# Sheet1.net
KiCad netlist of a schematic drawn in Altium Designer
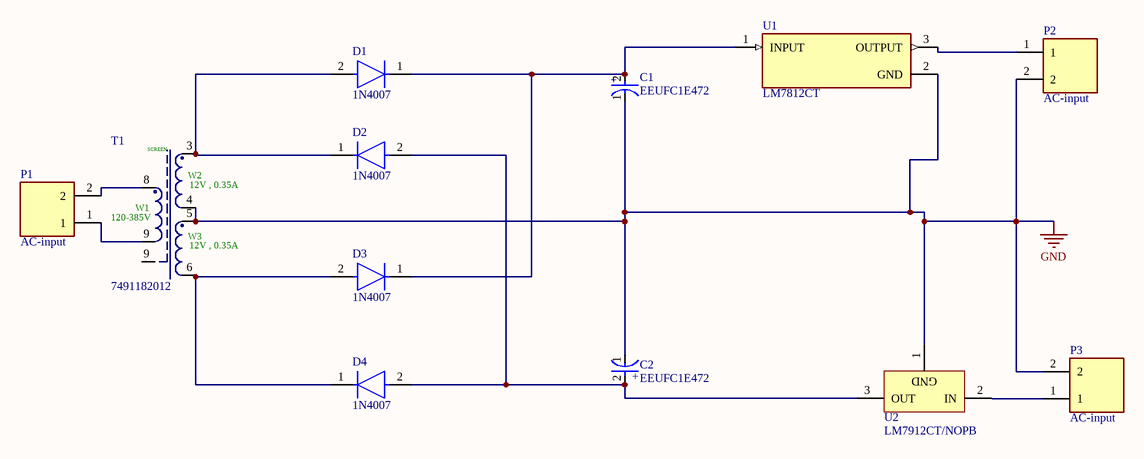
[diagram p0: Sheet1.SchDoc]

(export (version "E")
  (design (tool "Eeschema 10.0.6"))
  (components
    (comp (ref "C1")
      (value "EEUFC1E472")
      (footprint "FP-RAD-TH-D_18_0_5-L_35_5-MFG")
      (description "Aluminum Electrolytic Capacitors (Radial Lead Type) AEC-Q200 Qualified 4700uF ±20% 25V")
      (fields (field (name "VOLTAGE") "25V") (field (name "TOLERANCE") "20%"))
      (libsource (lib "Altium Content Vault") (part "203bc49f2ac43e59fd269a8c329ed05"))
    )
    (comp (ref "C2")
      (value "EEUFC1E472")
      (footprint "FP-RAD-TH-D_18_0_5-L_35_5-MFG")
      (description "Aluminum Electrolytic Capacitors (Radial Lead Type) AEC-Q200 Qualified 4700uF ±20% 25V")
      (fields (field (name "VOLTAGE") "25V") (field (name "TOLERANCE") "20%"))
      (libsource (lib "Altium Content Vault") (part "203bc49f2ac43e59fd269a8c329ed05"))
    )
    (comp (ref "D1")
      (value "1N4007")
      (footprint "FP-1N4007-MFG")
      (description "Rectifier diode 1000 V 1 A DO-41, ,")
      (fields
        (field (name "MANUFACTURER") "Diotec")
        (field (name "OCTOPART") "https://octopart.com/1n4007-diotec-4040411")
      )
      (libsource (lib "Altium Content Vault") (part "d7152d700b627762746794eb795d46e"))
    )
    (comp (ref "D2")
      (value "1N4007")
      (footprint "FP-1N4007-MFG")
      (description "Rectifier diode 1000 V 1 A DO-41, ,")
      (fields
        (field (name "MANUFACTURER") "Diotec")
        (field (name "OCTOPART") "https://octopart.com/1n4007-diotec-4040411")
      )
      (libsource (lib "Altium Content Vault") (part "d7152d700b627762746794eb795d46e"))
    )
    (comp (ref "D3")
      (value "1N4007")
      (footprint "FP-1N4007-MFG")
      (description "Rectifier diode 1000 V 1 A DO-41, ,")
      (fields
        (field (name "MANUFACTURER") "Diotec")
        (field (name "OCTOPART") "https://octopart.com/1n4007-diotec-4040411")
      )
      (libsource (lib "Altium Content Vault") (part "d7152d700b627762746794eb795d46e"))
    )
    (comp (ref "D4")
      (value "1N4007")
      (footprint "FP-1N4007-MFG")
      (description "Rectifier diode 1000 V 1 A DO-41, ,")
      (fields
        (field (name "MANUFACTURER") "Diotec")
        (field (name "OCTOPART") "https://octopart.com/1n4007-diotec-4040411")
      )
      (libsource (lib "Altium Content Vault") (part "d7152d700b627762746794eb795d46e"))
    )
    (comp (ref "P1")
      (value "AC-input")
      (footprint "HANDSON_KF301-2P")
      (description "2 Pin Terminal Block 5mm Pitch")
      (fields (field (name "MF") "Handson Technology") (field (name "MP") "KF301-2P"))
      (libsource (lib "") (part "KF301-2P_2"))
    )
    (comp (ref "P2")
      (value "AC-input")
      (footprint "HANDSON_KF301-2P")
      (description "2 Pin Terminal Block 5mm Pitch")
      (fields (field (name "MF") "Handson Technology") (field (name "MP") "KF301-2P"))
      (libsource (lib "KF301-2P") (part "KF301-2P"))
    )
    (comp (ref "P3")
      (value "AC-input")
      (footprint "HANDSON_KF301-2P")
      (description "2 Pin Terminal Block 5mm Pitch")
      (fields (field (name "MF") "Handson Technology") (field (name "MP") "KF301-2P"))
      (libsource (lib "") (part "KF301-2P_1"))
    )
    (comp (ref "T1")
      (value "7491182012")
      (footprint "EE16_7_4 (E16)")
      (description "Off-Line Transformer WE-UNIT , L=0.9mH")
      (fields (field (name "MANUFACTURER") "Wuerth Elektronik"))
      (libsource (lib "Altium Content Vault") (part "WE-7491182012"))
    )
    (comp (ref "U1")
      (value "LM7812CT")
      (footprint "FP-TO220B03-MFG")
      (description "IC REG LINEAR 12V 1A TO220-3")
      (fields
        (field (name "OCTOPART") "https://octopart.com/lm7812ct-on+semiconductor-14383031")
        (field (name "OBSOLETE PART") "true")
      )
      (libsource (lib "Altium Content Vault") (part "6207a8f1a6b4db326a9e0a8a99b4969"))
    )
    (comp (ref "U2")
      (value "LM7912CT/NOPB")
      (footprint "NDE0003A")
      (description "3-Terminal Negative Regulator, 3-pin TO-220, Pb-Free")
      (fields (field (name "MANUFACTURER") "Texas Instruments"))
      (libsource (lib "Altium Content Vault") (part "PM-REG-LM7905-SIL3"))
    )
  )
  (nets
    (net (code "1") (name "GND") (class "Default")
      (node (ref "C1") (pin "1") (pinfunction "C_1") (pintype "passive"))
      (node (ref "C2") (pin "1") (pinfunction "C_1") (pintype "passive"))
      (node (ref "P2") (pin "2") (pinfunction "2_2") (pintype "passive"))
      (node (ref "P3") (pin "2") (pinfunction "2_2") (pintype "passive"))
      (node (ref "T1") (pin "4") (pinfunction "4_4") (pintype "passive"))
      (node (ref "T1") (pin "5") (pinfunction "5_5") (pintype "passive"))
      (node (ref "U1") (pin "2") (pinfunction "GND_2") (pintype "power_in"))
      (node (ref "U2") (pin "1") (pinfunction "GND_1") (pintype "power_in"))
    )
    (net (code "2") (name "Net-(C1-A)") (class "Default")
      (node (ref "C1") (pin "2") (pinfunction "A_2") (pintype "passive"))
      (node (ref "D1") (pin "1") (pinfunction "C_1") (pintype "passive"))
      (node (ref "D3") (pin "1") (pinfunction "C_1") (pintype "passive"))
      (node (ref "U1") (pin "1") (pinfunction "INPUT_1") (pintype "input"))
    )
    (net (code "3") (name "Net-(C2-A)") (class "Default")
      (node (ref "C2") (pin "2") (pinfunction "A_2") (pintype "passive"))
      (node (ref "D2") (pin "2") (pinfunction "A_2") (pintype "passive"))
      (node (ref "D4") (pin "2") (pinfunction "A_2") (pintype "passive"))
      (node (ref "U2") (pin "3") (pinfunction "OUT_3") (pintype "power_in"))
    )
    (net (code "4") (name "Net-(D1-A)") (class "Default")
      (node (ref "D1") (pin "2") (pinfunction "A_2") (pintype "passive"))
      (node (ref "D2") (pin "1") (pinfunction "C_1") (pintype "passive"))
      (node (ref "T1") (pin "3") (pinfunction "3_3") (pintype "passive"))
    )
    (net (code "5") (name "Net-(D3-A)") (class "Default")
      (node (ref "D3") (pin "2") (pinfunction "A_2") (pintype "passive"))
      (node (ref "D4") (pin "1") (pinfunction "C_1") (pintype "passive"))
      (node (ref "T1") (pin "6") (pinfunction "6_6") (pintype "passive"))
    )
    (net (code "6") (name "Net-(P1-Pad1)") (class "Default")
      (node (ref "P1") (pin "1") (pinfunction "1_1") (pintype "passive"))
      (node (ref "T1") (pin "9") (pinfunction "9_9") (pintype "passive"))
    )
    (net (code "7") (name "Net-(P1-Pad2)") (class "Default")
      (node (ref "P1") (pin "2") (pinfunction "2_2") (pintype "passive"))
      (node (ref "T1") (pin "8") (pinfunction "8_8") (pintype "passive"))
    )
    (net (code "8") (name "Net-(U1-OUTPUT)") (class "Default")
      (node (ref "P2") (pin "1") (pinfunction "1_1") (pintype "passive"))
      (node (ref "U1") (pin "3") (pinfunction "OUTPUT_3") (pintype "output"))
    )
    (net (code "9") (name "Net-(U2-IN)") (class "Default")
      (node (ref "P3") (pin "1") (pinfunction "1_1") (pintype "passive"))
      (node (ref "U2") (pin "2") (pinfunction "IN_2") (pintype "power_in"))
    )
    (net (code "10") (name "unconnected-(T1-Pad9)") (class "Default")
      (node (ref "T1") (pin "9") (pinfunction "9_9") (pintype "passive"))
    )
  )
)
